# SparkFun_5-Way_Tactile_Switch_Breakout.net
KiCad netlist of a schematic drawn in EAGLE
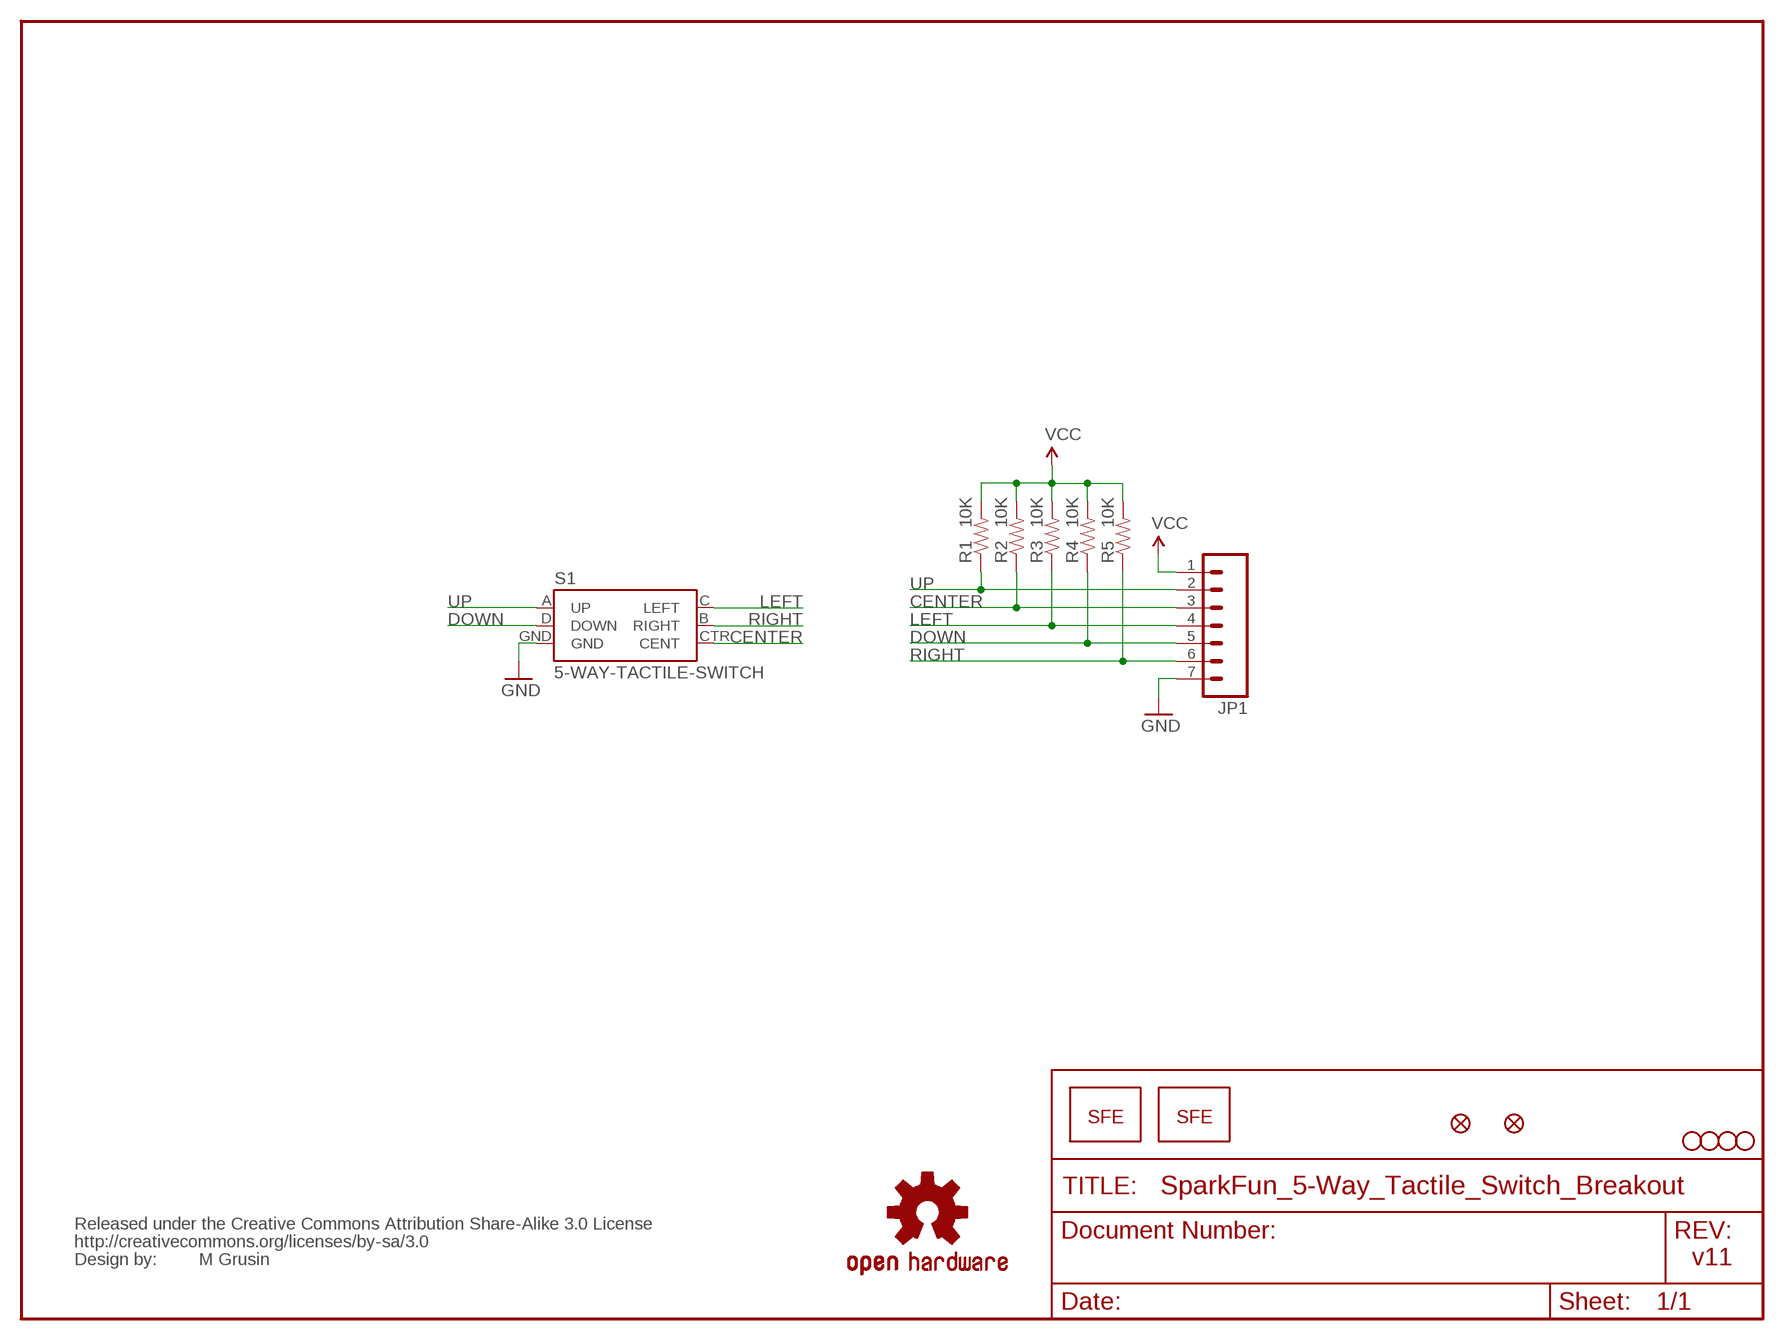
[diagram p0: schematic, sheet 1]

(export (version "E")
  (design (tool "Eeschema 10.0.6"))
  (components
    (comp (ref "JP1")
      (value "M07")
      (footprint "eagle-import:1X07")
      (libsource (lib "eagle-import") (part "M07"))
    )
    (comp (ref "JP2")
      (value "FIDUCIALUFIDUCIAL")
      (footprint "eagle-import:MICRO-FIDUCIAL")
      (libsource (lib "eagle-import") (part "FIDUCIALUFIDUCIAL"))
    )
    (comp (ref "JP3")
      (value "STAND-OFF")
      (footprint "eagle-import:STAND-OFF")
      (libsource (lib "eagle-import") (part "STAND-OFF"))
    )
    (comp (ref "JP4")
      (value "STAND-OFF")
      (footprint "eagle-import:STAND-OFF")
      (libsource (lib "eagle-import") (part "STAND-OFF"))
    )
    (comp (ref "JP5")
      (value "STAND-OFF")
      (footprint "eagle-import:STAND-OFF")
      (libsource (lib "eagle-import") (part "STAND-OFF"))
    )
    (comp (ref "JP6")
      (value "STAND-OFF")
      (footprint "eagle-import:STAND-OFF")
      (libsource (lib "eagle-import") (part "STAND-OFF"))
    )
    (comp (ref "JP7")
      (value "FIDUCIALUFIDUCIAL")
      (footprint "eagle-import:MICRO-FIDUCIAL")
      (libsource (lib "eagle-import") (part "FIDUCIALUFIDUCIAL"))
    )
    (comp (ref "JP9")
      (value "LOGO-SFESK")
      (footprint "eagle-import:SFE-LOGO-FLAME")
      (libsource (lib "eagle-import") (part "LOGO-SFESK"))
    )
    (comp (ref "JP10")
      (value "LOGO-SFENW2")
      (footprint "eagle-import:SFE-NEW-WEB")
      (libsource (lib "eagle-import") (part "LOGO-SFENW2"))
    )
    (comp (ref "R1")
      (value "10K")
      (footprint "eagle-import:0603-RES")
      (libsource (lib "eagle-import") (part "RESISTOR0603-RES"))
    )
    (comp (ref "R2")
      (value "10K")
      (footprint "eagle-import:0603-RES")
      (libsource (lib "eagle-import") (part "RESISTOR0603-RES"))
    )
    (comp (ref "R3")
      (value "10K")
      (footprint "eagle-import:0603-RES")
      (libsource (lib "eagle-import") (part "RESISTOR0603-RES"))
    )
    (comp (ref "R4")
      (value "10K")
      (footprint "eagle-import:0603-RES")
      (libsource (lib "eagle-import") (part "RESISTOR0603-RES"))
    )
    (comp (ref "R5")
      (value "10K")
      (footprint "eagle-import:0603-RES")
      (libsource (lib "eagle-import") (part "RESISTOR0603-RES"))
    )
    (comp (ref "S1")
      (value "5-WAY-TACTILE-SWITCH")
      (footprint "eagle-import:JOYSTICK_MINI")
      (libsource (lib "eagle-import") (part "JOYSTICK_MINI"))
    )
    (comp (ref "U$1")
      (value "OSHW-LOGOS")
      (footprint "eagle-import:OSHW-LOGO-S")
      (libsource (lib "eagle-import") (part "OSHW-LOGOS"))
    )
    (comp (ref "U$2")
      (value "CREATIVE_COMMONS")
      (footprint "eagle-import:CREATIVE_COMMONS")
      (libsource (lib "eagle-import") (part "CREATIVE_COMMONS"))
    )
  )
  (nets
    (net (code "1") (name "/CENTER") (class "Default")
      (node (ref "JP1") (pin "3") (pinfunction "3_3") (pintype "passive"))
      (node (ref "R2") (pin "1") (pinfunction "1_1") (pintype "passive"))
      (node (ref "S1") (pin "CTR") (pinfunction "CENT_CTR") (pintype "bidirectional"))
    )
    (net (code "2") (name "/DOWN") (class "Default")
      (node (ref "JP1") (pin "5") (pinfunction "5_5") (pintype "passive"))
      (node (ref "R4") (pin "1") (pinfunction "1_1") (pintype "passive"))
      (node (ref "S1") (pin "D") (pinfunction "DOWN_D") (pintype "bidirectional"))
    )
    (net (code "3") (name "/LEFT") (class "Default")
      (node (ref "JP1") (pin "4") (pinfunction "4_4") (pintype "passive"))
      (node (ref "R3") (pin "1") (pinfunction "1_1") (pintype "passive"))
      (node (ref "S1") (pin "C") (pinfunction "LEFT_C") (pintype "bidirectional"))
    )
    (net (code "4") (name "/RIGHT") (class "Default")
      (node (ref "JP1") (pin "6") (pinfunction "6_6") (pintype "passive"))
      (node (ref "R5") (pin "1") (pinfunction "1_1") (pintype "passive"))
      (node (ref "S1") (pin "B") (pinfunction "RIGHT_B") (pintype "bidirectional"))
    )
    (net (code "5") (name "/UP") (class "Default")
      (node (ref "JP1") (pin "2") (pinfunction "2_2") (pintype "passive"))
      (node (ref "R1") (pin "1") (pinfunction "1_1") (pintype "passive"))
      (node (ref "S1") (pin "A") (pinfunction "UP_A") (pintype "bidirectional"))
    )
    (net (code "6") (name "GND") (class "Default")
      (node (ref "JP1") (pin "7") (pinfunction "7_7") (pintype "passive"))
      (node (ref "S1") (pin "GND") (pinfunction "GND_GND") (pintype "bidirectional"))
    )
    (net (code "7") (name "VCC") (class "Default")
      (node (ref "JP1") (pin "1") (pinfunction "1_1") (pintype "passive"))
      (node (ref "R1") (pin "2") (pinfunction "2_2") (pintype "passive"))
      (node (ref "R2") (pin "2") (pinfunction "2_2") (pintype "passive"))
      (node (ref "R3") (pin "2") (pinfunction "2_2") (pintype "passive"))
      (node (ref "R4") (pin "2") (pinfunction "2_2") (pintype "passive"))
      (node (ref "R5") (pin "2") (pinfunction "2_2") (pintype "passive"))
    )
  )
)
